# I2C_ISO.net
KiCad netlist of a schematic drawn in Altium Designer
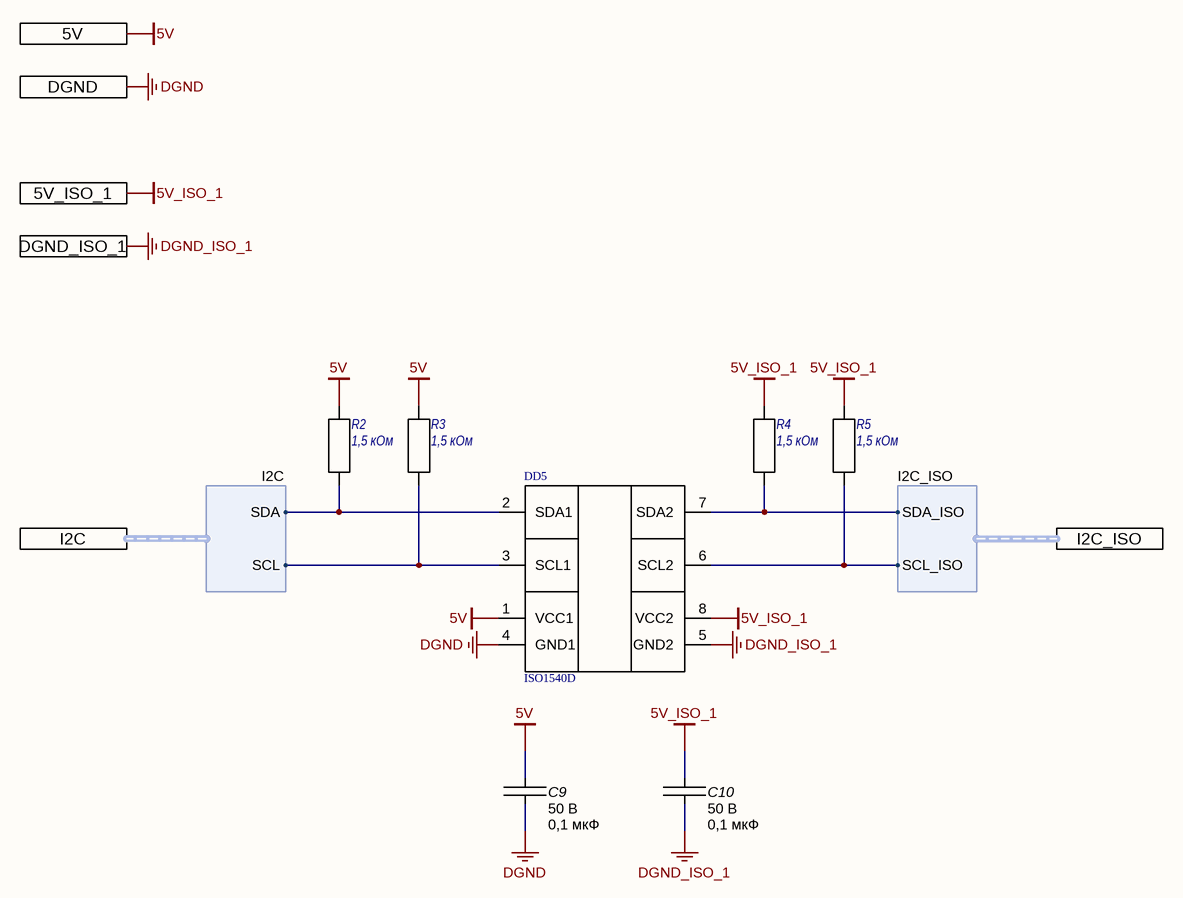
[diagram p0: I2C_ISO.SchDoc]

(export (version "E")
  (design (tool "Eeschema 10.0.6"))
  (components
    (comp (ref "C9")
      (value "0,1 мкФ")
      (footprint "C0603C")
      (description "SMD 0603 ; X7R; 0,1 мкФ; 50 В")
      (fields
        (field (name "PART NUMBER") "CC0603KRX7R9BB104")
        (field (name "MANUFACTURER") "YAGEO")
        (field (name "VOLTAGE") "50 В")
      )
      (libsource (lib "Capacitors") (part "CC0603KRX7R9BB104"))
    )
    (comp (ref "C10")
      (value "0,1 мкФ")
      (footprint "C0603C")
      (description "SMD 0603 ; X7R; 0,1 мкФ; 50 В")
      (fields
        (field (name "PART NUMBER") "CC0603KRX7R9BB104")
        (field (name "MANUFACTURER") "YAGEO")
        (field (name "VOLTAGE") "50 В")
      )
      (libsource (lib "Capacitors") (part "CC0603KRX7R9BB104"))
    )
    (comp (ref "DD5")
      (value "ISO1540D")
      (footprint "SOIC-8")
      (description "I2C ISO")
      (fields (field (name "MANUFACTURER") "Texas Instruments"))
      (libsource (lib "IC") (part "ISO1540D"))
    )
    (comp (ref "R2")
      (value "1,5 кОм")
      (footprint "C0603R")
      (description "SMD 0603; 0,1; 1%; 1,5 кОм")
      (fields (field (name "PART NUMBER") "RC0603FR-071K5L") (field (name "POWER") "0,1"))
      (libsource (lib "Resistors") (part "RC0603FR-071K5L"))
    )
    (comp (ref "R3")
      (value "1,5 кОм")
      (footprint "C0603R")
      (description "SMD 0603; 0,1; 1%; 1,5 кОм")
      (fields (field (name "PART NUMBER") "RC0603FR-071K5L") (field (name "POWER") "0,1"))
      (libsource (lib "Resistors") (part "RC0603FR-071K5L"))
    )
    (comp (ref "R4")
      (value "1,5 кОм")
      (footprint "C0603R")
      (description "SMD 0603; 0,1; 1%; 1,5 кОм")
      (fields (field (name "PART NUMBER") "RC0603FR-071K5L") (field (name "POWER") "0,1"))
      (libsource (lib "Resistors") (part "RC0603FR-071K5L"))
    )
    (comp (ref "R5")
      (value "1,5 кОм")
      (footprint "C0603R")
      (description "SMD 0603; 0,1; 1%; 1,5 кОм")
      (fields (field (name "PART NUMBER") "RC0603FR-071K5L") (field (name "POWER") "0,1"))
      (libsource (lib "Resistors") (part "RC0603FR-071K5L"))
    )
  )
  (nets
    (net (code "5") (name "5V") (class "Default")
      (node (ref "C9") (pin "1") (pinfunction "1_1") (pintype "passive"))
      (node (ref "DD5") (pin "1") (pinfunction "VCC1_1") (pintype "passive"))
      (node (ref "R2") (pin "2") (pinfunction "2_2") (pintype "passive"))
      (node (ref "R3") (pin "2") (pinfunction "2_2") (pintype "passive"))
    )
    (net (code "6") (name "5V_ISO_1") (class "Default")
      (node (ref "C10") (pin "1") (pinfunction "1_1") (pintype "passive"))
      (node (ref "DD5") (pin "8") (pinfunction "VCC2_8") (pintype "passive"))
      (node (ref "R4") (pin "2") (pinfunction "2_2") (pintype "passive"))
      (node (ref "R5") (pin "2") (pinfunction "2_2") (pintype "passive"))
    )
    (net (code "7") (name "DGND") (class "Default")
      (node (ref "C9") (pin "2") (pinfunction "2_2") (pintype "passive"))
      (node (ref "DD5") (pin "4") (pinfunction "GND1_4") (pintype "passive"))
    )
    (net (code "8") (name "DGND_ISO_1") (class "Default")
      (node (ref "C10") (pin "2") (pinfunction "2_2") (pintype "passive"))
      (node (ref "DD5") (pin "5") (pinfunction "GND2_5") (pintype "passive"))
    )
    (net (code "9") (name "Net-(DD5-SCL1)") (class "Default")
      (node (ref "DD5") (pin "3") (pinfunction "SCL1_3") (pintype "passive"))
      (node (ref "R3") (pin "1") (pinfunction "1_1") (pintype "passive"))
    )
    (net (code "10") (name "Net-(DD5-SCL2)") (class "Default")
      (node (ref "DD5") (pin "6") (pinfunction "SCL2_6") (pintype "passive"))
      (node (ref "R5") (pin "1") (pinfunction "1_1") (pintype "passive"))
    )
    (net (code "11") (name "Net-(DD5-SDA1)") (class "Default")
      (node (ref "DD5") (pin "2") (pinfunction "SDA1_2") (pintype "passive"))
      (node (ref "R2") (pin "1") (pinfunction "1_1") (pintype "passive"))
    )
    (net (code "12") (name "Net-(DD5-SDA2)") (class "Default")
      (node (ref "DD5") (pin "7") (pinfunction "SDA2_7") (pintype "passive"))
      (node (ref "R4") (pin "1") (pinfunction "1_1") (pintype "passive"))
    )
  )
)
